# ATTiny85_Binary_Counter.net
KiCad netlist of a schematic drawn in EasyEDA
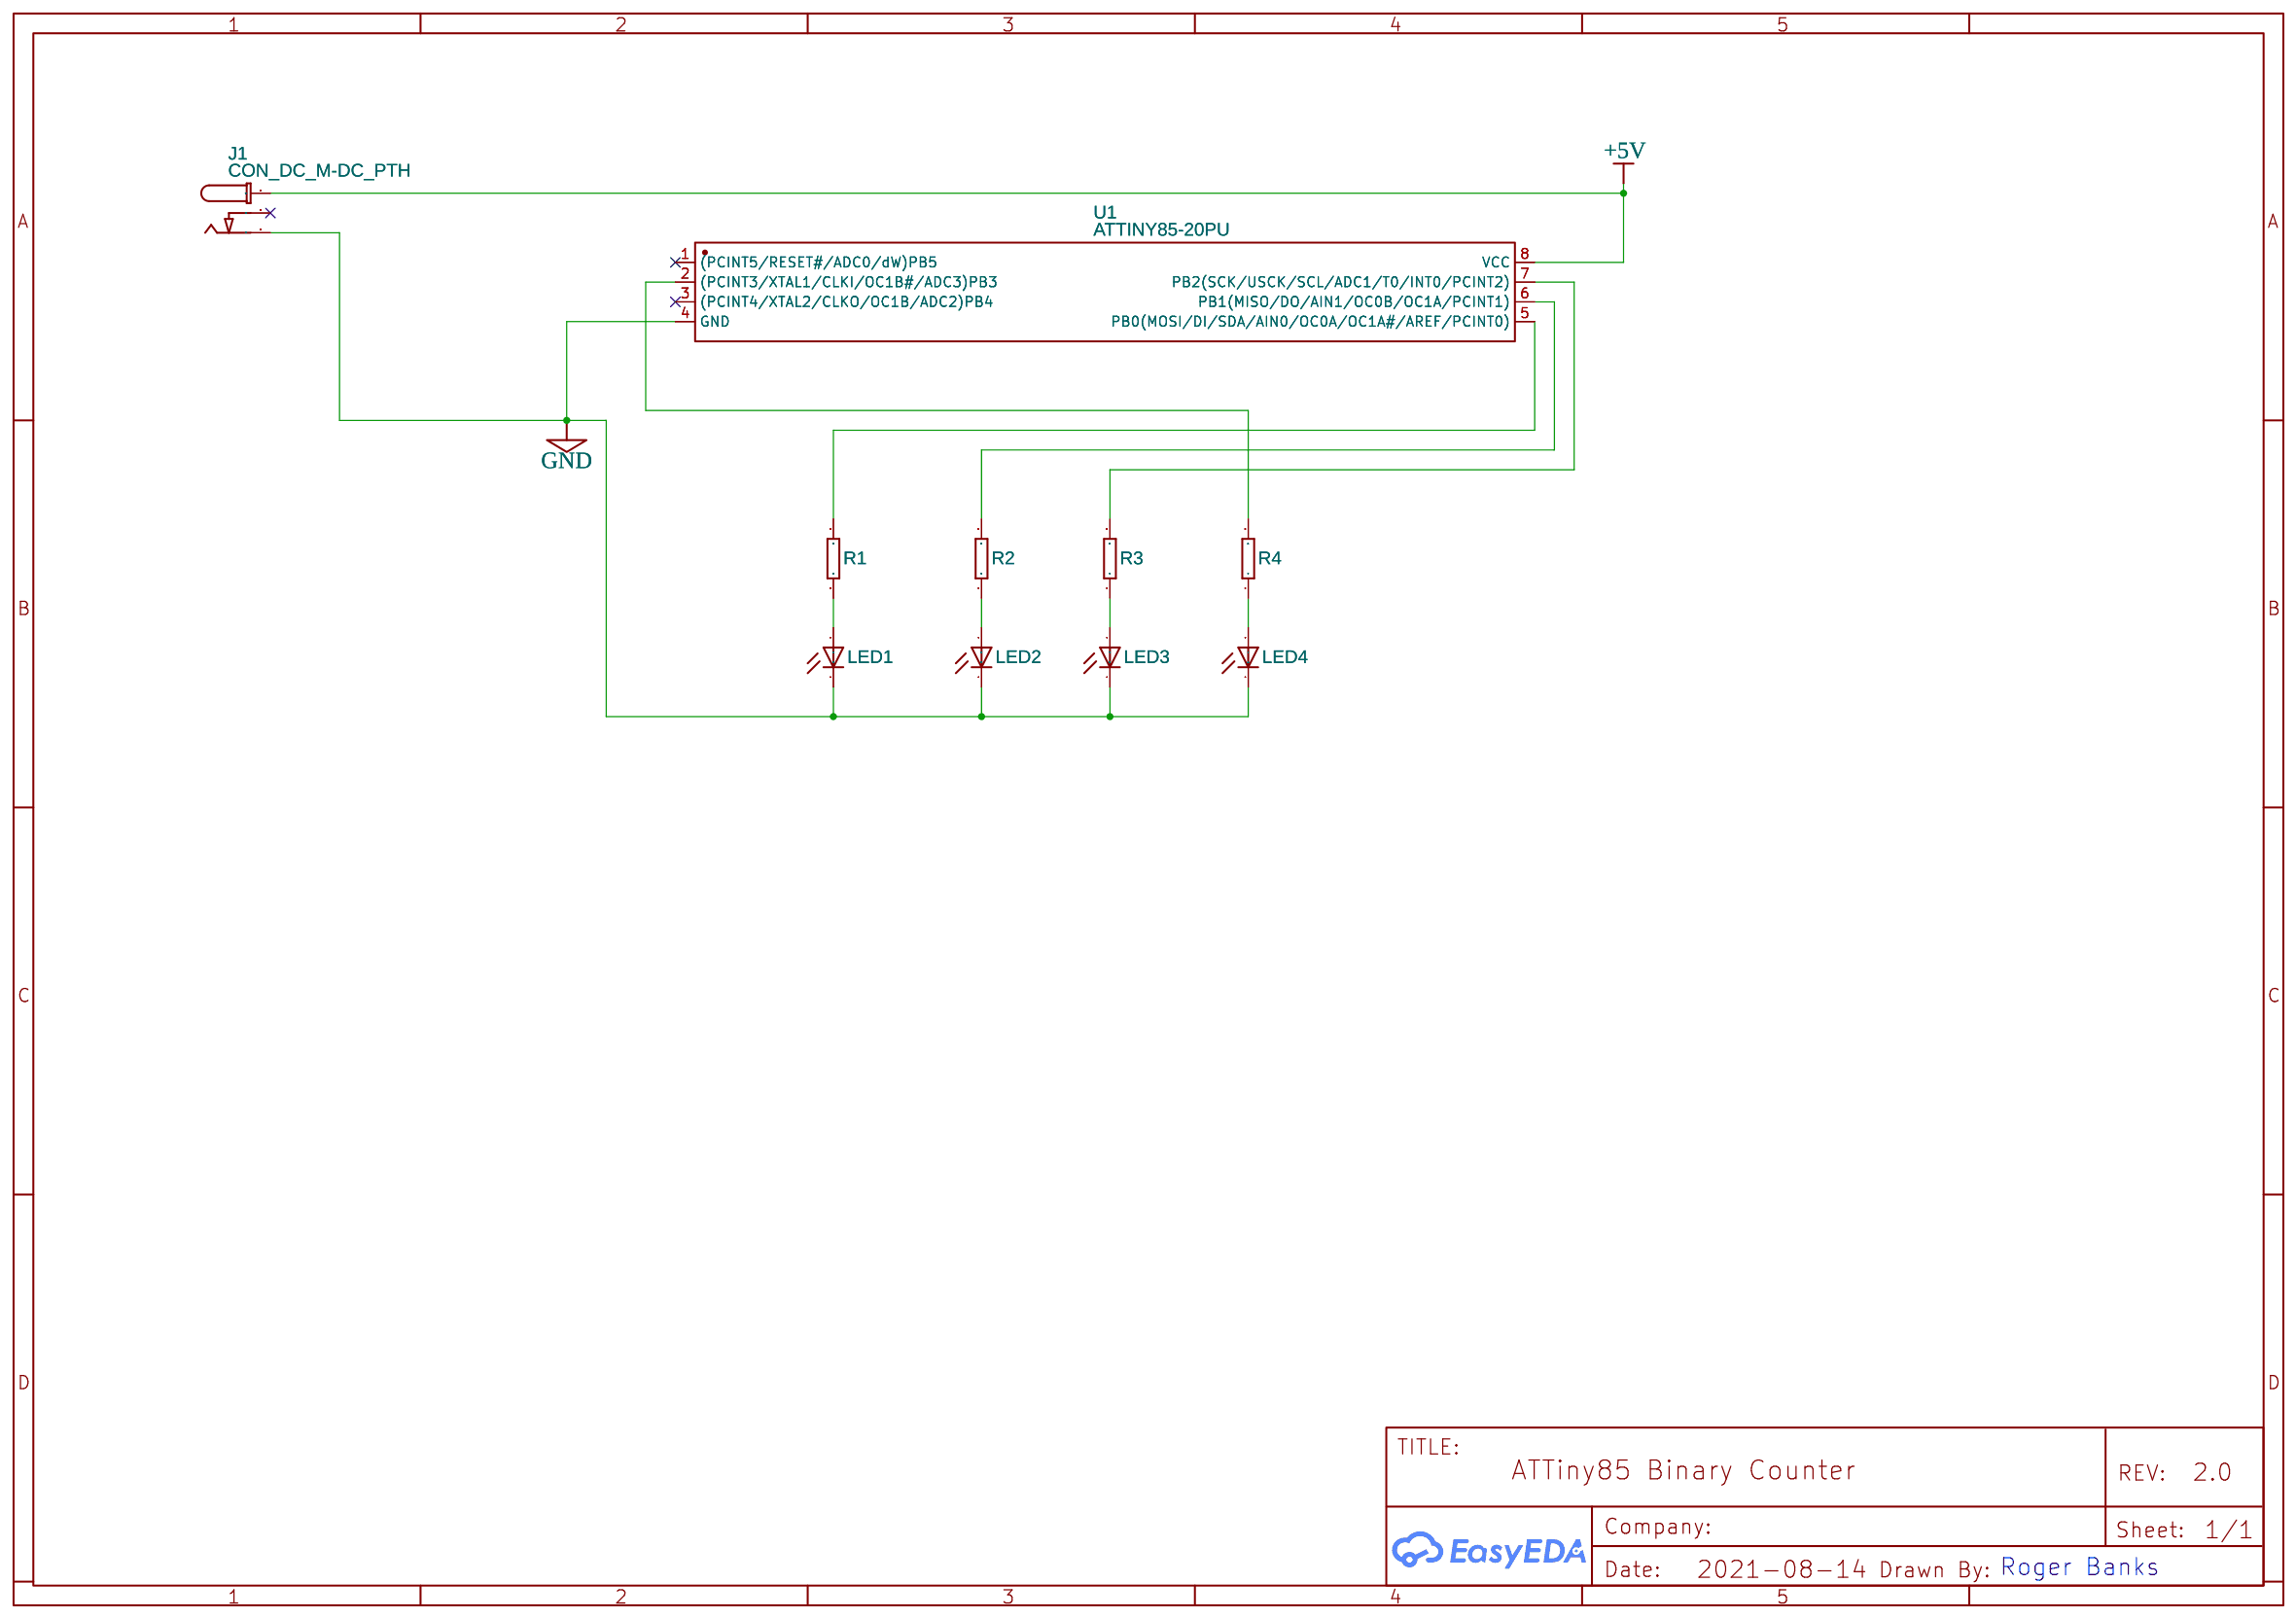
[diagram p0: schematic sheet]

(export (version "E")
  (design (tool "Eeschema 10.0.6"))
  (components
    (comp (ref "J1") (value "CON_DC_M-DC_PTH") (libsource (lib "") (part "CON_DC_M-DC_PTH")))
    (comp (ref "LED1") (value "LED5MM") (libsource (lib "") (part "LED5MM")))
    (comp (ref "LED2") (value "LED5MM") (libsource (lib "") (part "LED5MM")))
    (comp (ref "LED3") (value "LED5MM") (libsource (lib "") (part "LED5MM")))
    (comp (ref "LED4") (value "LED5MM") (libsource (lib "") (part "LED5MM")))
    (comp (ref "R1") (value "RESISTOR") (libsource (lib "") (part "RESISTOR")))
    (comp (ref "R2") (value "RESISTOR") (libsource (lib "") (part "RESISTOR")))
    (comp (ref "R3") (value "RESISTOR") (libsource (lib "") (part "RESISTOR")))
    (comp (ref "R4") (value "RESISTOR") (libsource (lib "") (part "RESISTOR")))
    (comp (ref "U1")
      (value "ATTINY85-20PU")
      (fields (field (name "BOM_Supplier Part") "C965497"))
      (libsource (lib "") (part "ATTINY85-20PU"))
    )
  )
  (nets
    (net (code "1") (name "+5V") (class "Default")
      (node (ref "J1") (pin "P1") (pinfunction "P1_P1") (pintype "unspecified"))
      (node (ref "U1") (pin "8") (pinfunction "VCC_8") (pintype "unspecified"))
    )
    (net (code "2") (name "GND") (class "Default")
      (node (ref "J1") (pin "P3") (pinfunction "P2_P3") (pintype "unspecified"))
      (node (ref "LED1") (pin "K") (pinfunction "C_K") (pintype "unspecified"))
      (node (ref "LED2") (pin "K") (pinfunction "C_K") (pintype "unspecified"))
      (node (ref "LED3") (pin "K") (pinfunction "C_K") (pintype "unspecified"))
      (node (ref "LED4") (pin "K") (pinfunction "C_K") (pintype "unspecified"))
      (node (ref "U1") (pin "4") (pinfunction "GND_4") (pintype "unspecified"))
    )
    (net (code "3") (name "Net-(LED1-PadA)") (class "Default")
      (node (ref "LED1") (pin "A") (pinfunction "A_A") (pintype "unspecified"))
      (node (ref "R1") (pin "1") (pinfunction "1_1") (pintype "unspecified"))
    )
    (net (code "4") (name "Net-(LED2-PadA)") (class "Default")
      (node (ref "LED2") (pin "A") (pinfunction "A_A") (pintype "unspecified"))
      (node (ref "R2") (pin "1") (pinfunction "1_1") (pintype "unspecified"))
    )
    (net (code "5") (name "Net-(LED3-PadA)") (class "Default")
      (node (ref "LED3") (pin "A") (pinfunction "A_A") (pintype "unspecified"))
      (node (ref "R3") (pin "1") (pinfunction "1_1") (pintype "unspecified"))
    )
    (net (code "6") (name "Net-(LED4-PadA)") (class "Default")
      (node (ref "LED4") (pin "A") (pinfunction "A_A") (pintype "unspecified"))
      (node (ref "R4") (pin "1") (pinfunction "1_1") (pintype "unspecified"))
    )
    (net (code "7") (name "Net-(U1-(PCINT3{slash}XTAL1{slash}CLKI{slash}OC1B#{slash}ADC3)PB3)") (class "Default")
      (node (ref "R4") (pin "2") (pinfunction "2_2") (pintype "unspecified"))
      (node (ref "U1") (pin "2") (pinfunction "(PCINT3/XTAL1/CLKI/OC1B#/ADC3)PB3_2") (pintype "unspecified"))
    )
    (net (code "8") (name "Net-(U1-PB0(MOSI{slash}DI{slash}SDA{slash}AIN0{slash}OC0A{slash}OC1A#{slash}AREF{slash}PCINT0))") (class "Default")
      (node (ref "R1") (pin "2") (pinfunction "2_2") (pintype "unspecified"))
      (node (ref "U1") (pin "5") (pinfunction "PB0(MOSI/DI/SDA/AIN0/OC0A/OC1A#/AREF/PCINT0)_5") (pintype "unspecified"))
    )
    (net (code "9") (name "Net-(U1-PB1(MISO{slash}DO{slash}AIN1{slash}OC0B{slash}OC1A{slash}PCINT1))") (class "Default")
      (node (ref "R2") (pin "2") (pinfunction "2_2") (pintype "unspecified"))
      (node (ref "U1") (pin "6") (pinfunction "PB1(MISO/DO/AIN1/OC0B/OC1A/PCINT1)_6") (pintype "unspecified"))
    )
    (net (code "10") (name "Net-(U1-PB2(SCK{slash}USCK{slash}SCL{slash}ADC1{slash}T0{slash}INT0{slash}PCINT2))") (class "Default")
      (node (ref "R3") (pin "2") (pinfunction "2_2") (pintype "unspecified"))
      (node (ref "U1") (pin "7") (pinfunction "PB2(SCK/USCK/SCL/ADC1/T0/INT0/PCINT2)_7") (pintype "unspecified"))
    )
    (net (code "11") (name "unconnected-(J1-P3-PadP2)") (class "Default")
      (node (ref "J1") (pin "P2") (pinfunction "P3_P2") (pintype "unspecified+no_connect"))
    )
    (net (code "12") (name "unconnected-(U1-(PCINT4{slash}XTAL2{slash}CLKO{slash}OC1B{slash}ADC2)PB4-Pad3)") (class "Default")
      (node (ref "U1") (pin "3") (pinfunction "(PCINT4/XTAL2/CLKO/OC1B/ADC2)PB4_3") (pintype "unspecified+no_connect"))
    )
    (net (code "13") (name "unconnected-(U1-(PCINT5{slash}RESET#{slash}ADC0{slash}dW)PB5-Pad1)") (class "Default")
      (node (ref "U1") (pin "1") (pinfunction "(PCINT5/RESET#/ADC0/dW)PB5_1") (pintype "unspecified+no_connect"))
    )
  )
)
